# WM8731_STM32F405_Featherwing.net
KiCad netlist of a schematic drawn in EAGLE
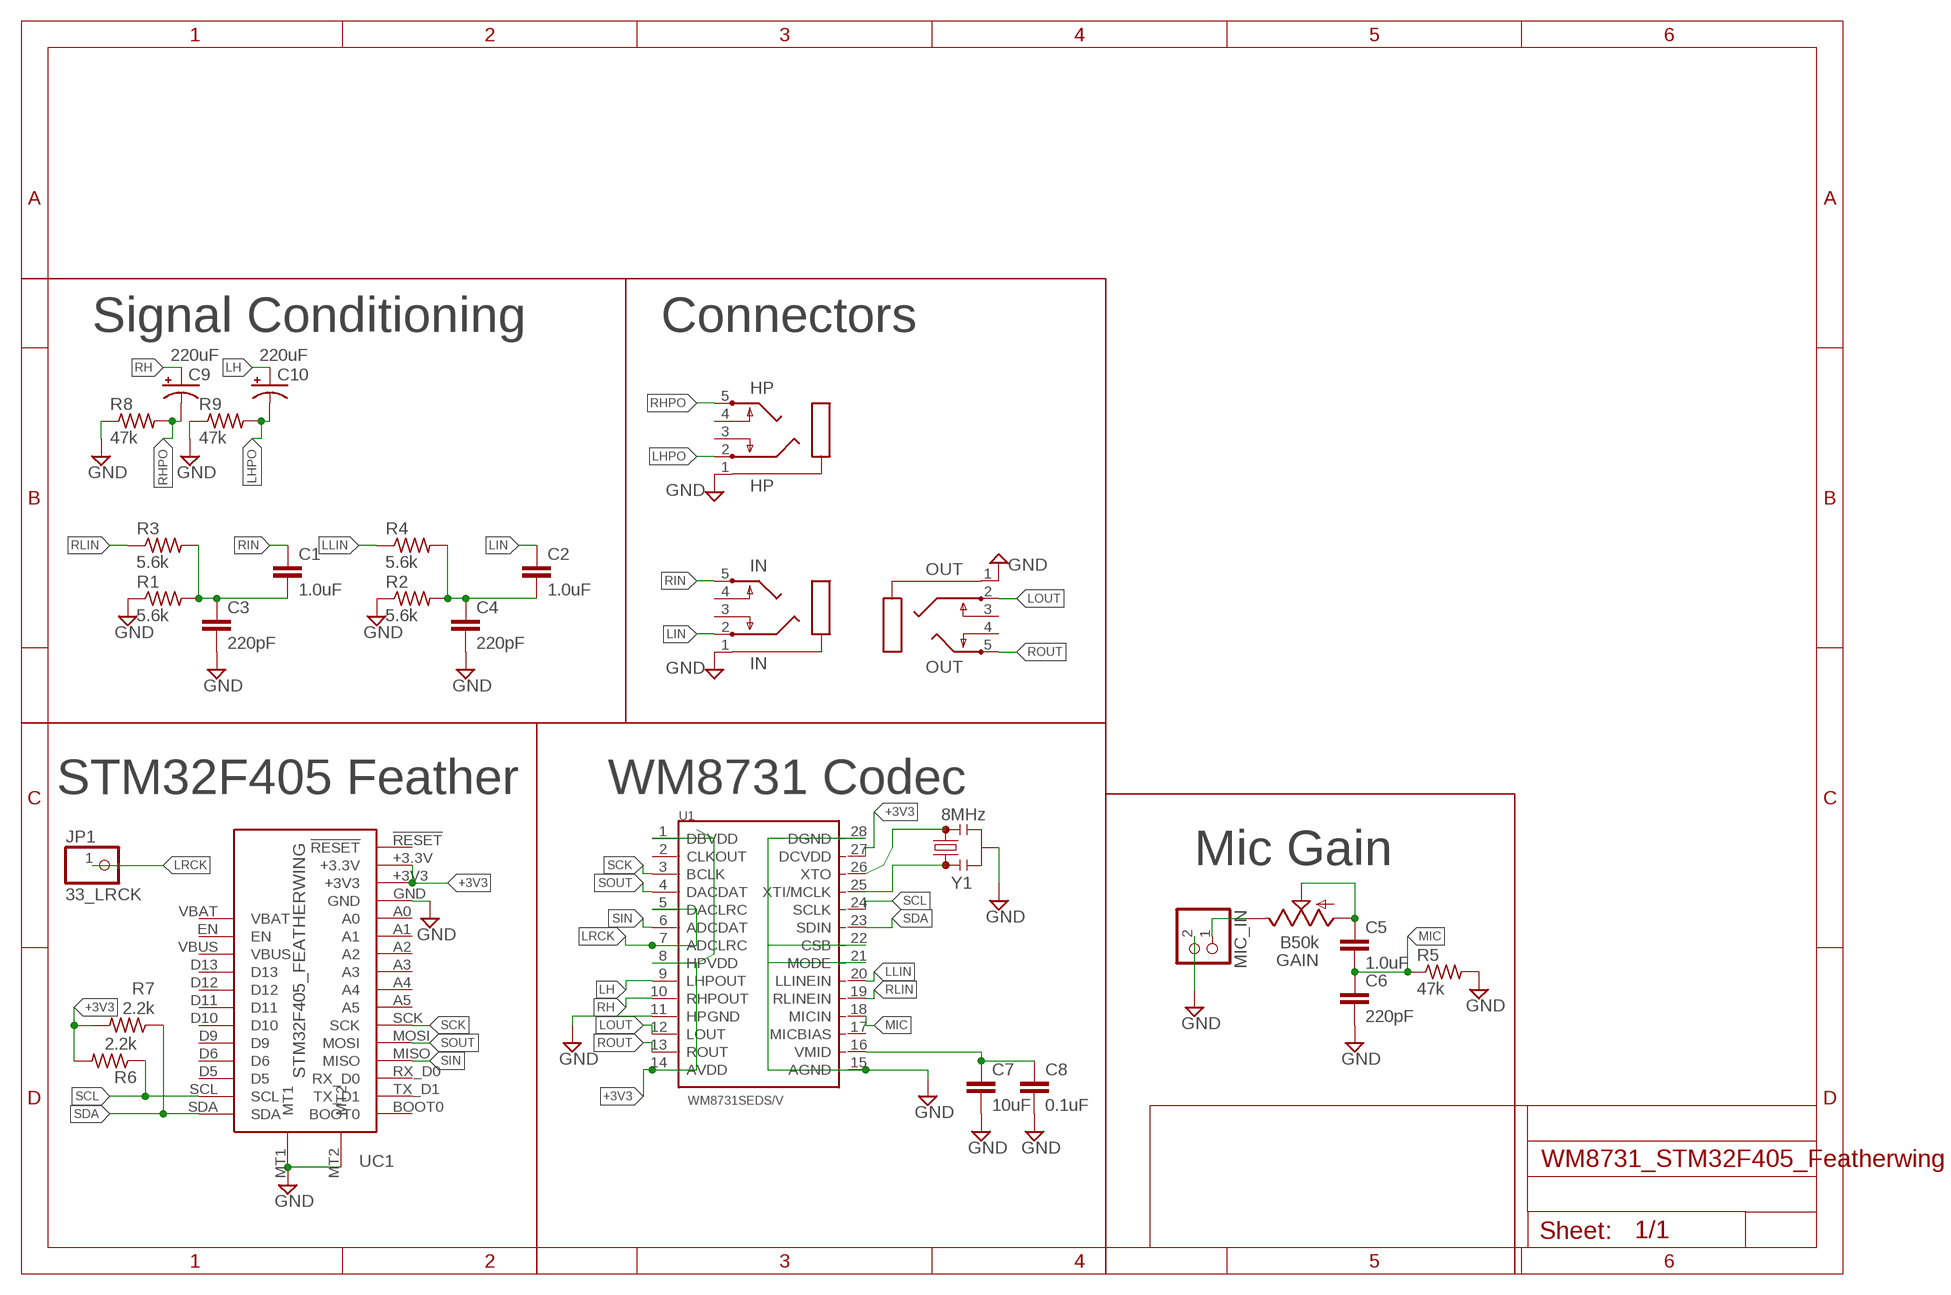
[diagram p0: schematic, sheet 1]

(export (version "E")
  (design (tool "Eeschema 10.0.6"))
  (components
    (comp (ref "C1")
      (value "1.0uF")
      (footprint "eagle-import:0402")
      (libsource (lib "eagle-import") (part "1.0UF-0402-16V-10%"))
    )
    (comp (ref "C2")
      (value "1.0uF")
      (footprint "eagle-import:0402")
      (libsource (lib "eagle-import") (part "1.0UF-0402-16V-10%"))
    )
    (comp (ref "C3")
      (value "220pF")
      (footprint "eagle-import:0402")
      (libsource (lib "eagle-import") (part "1.0UF-0402-16V-10%"))
    )
    (comp (ref "C4")
      (value "220pF")
      (footprint "eagle-import:0402")
      (libsource (lib "eagle-import") (part "1.0UF-0402-16V-10%"))
    )
    (comp (ref "C5")
      (value "1.0uF")
      (footprint "eagle-import:0402")
      (libsource (lib "eagle-import") (part "1.0UF-0402-16V-10%"))
    )
    (comp (ref "C6")
      (value "220pF")
      (footprint "eagle-import:0402")
      (libsource (lib "eagle-import") (part "1.0UF-0402-16V-10%"))
    )
    (comp (ref "C7")
      (value "10uF")
      (footprint "eagle-import:0603")
      (libsource (lib "eagle-import") (part "10UF-0603-6.3V-20%"))
    )
    (comp (ref "C8")
      (value "0.1uF")
      (footprint "eagle-import:0402")
      (libsource (lib "eagle-import") (part "0.1UF-0402-16V-10%"))
    )
    (comp (ref "C9")
      (value "220uF")
      (footprint "eagle-import:PANASONIC_D")
      (libsource (lib "eagle-import") (part "100UF-POLAR-25V-20%(ELEC)"))
    )
    (comp (ref "C10")
      (value "220uF")
      (footprint "eagle-import:PANASONIC_D")
      (libsource (lib "eagle-import") (part "100UF-POLAR-25V-20%(ELEC)"))
    )
    (comp (ref "GAIN")
      (value "B50k")
      (footprint "eagle-import:9MM_SNAP-IN_POT")
      (libsource (lib "eagle-import") (part "9MM_SNAP-IN_POT_"))
    )
    (comp (ref "HP")
      (value "HP")
      (footprint "eagle-import:STX3100")
      (libsource (lib "eagle-import") (part "STEREOJACK"))
    )
    (comp (ref "IN")
      (value "IN")
      (footprint "eagle-import:STX3100")
      (libsource (lib "eagle-import") (part "STEREOJACK"))
    )
    (comp (ref "JP1")
      (value "33_LRCK")
      (footprint "eagle-import:1X01")
      (libsource (lib "eagle-import") (part "PINHD-1X1"))
    )
    (comp (ref "MIC_IN")
      (value "PINHD-1X2")
      (footprint "eagle-import:1X02")
      (libsource (lib "eagle-import") (part "PINHD-1X2"))
    )
    (comp (ref "OUT")
      (value "OUT")
      (footprint "eagle-import:STX3100")
      (libsource (lib "eagle-import") (part "STEREOJACK"))
    )
    (comp (ref "R1")
      (value "5.6k")
      (footprint "eagle-import:R0402")
      (libsource (lib "eagle-import") (part "R-US_R0402"))
    )
    (comp (ref "R2")
      (value "5.6k")
      (footprint "eagle-import:R0402")
      (libsource (lib "eagle-import") (part "R-US_R0402"))
    )
    (comp (ref "R3")
      (value "5.6k")
      (footprint "eagle-import:R0402")
      (libsource (lib "eagle-import") (part "R-US_R0402"))
    )
    (comp (ref "R4")
      (value "5.6k")
      (footprint "eagle-import:R0402")
      (libsource (lib "eagle-import") (part "R-US_R0402"))
    )
    (comp (ref "R5")
      (value "47k")
      (footprint "eagle-import:R0402")
      (libsource (lib "eagle-import") (part "R-US_R0402"))
    )
    (comp (ref "R6")
      (value "2.2k")
      (footprint "eagle-import:R0402")
      (libsource (lib "eagle-import") (part "R-US_R0402"))
    )
    (comp (ref "R7")
      (value "2.2k")
      (footprint "eagle-import:R0402")
      (libsource (lib "eagle-import") (part "R-US_R0402"))
    )
    (comp (ref "R8")
      (value "47k")
      (footprint "eagle-import:R0402")
      (libsource (lib "eagle-import") (part "R-US_R0402"))
    )
    (comp (ref "R9")
      (value "47k")
      (footprint "eagle-import:R0402")
      (libsource (lib "eagle-import") (part "R-US_R0402"))
    )
    (comp (ref "U1")
      (value "WM8731SEDS/V")
      (footprint "eagle-import:SSOP28-0.65-10.2X5.2MM")
      (fields (field (name "MF") "Cirrus Logic"))
      (libsource (lib "eagle-import") (part "CODECODER-WM8731SEDS/V(SSOP28)"))
    )
    (comp (ref "UC1")
      (value "STM32F405_FEATHERWING")
      (footprint "eagle-import:STM32F405_FEATHERWING")
      (libsource (lib "eagle-import") (part "STM32F405_FEATHERWING"))
    )
    (comp (ref "Y1")
      (value "8MHz")
      (footprint "eagle-import:RESONATOR-SMD-3.2X1.3")
      (libsource (lib "eagle-import") (part "RESONATOR-8MHZSMD_3.2X1.3"))
    )
  )
  (nets
    (net (code "1") (name "+3V3") (class "Default")
      (node (ref "R6") (pin "2") (pinfunction "2_2") (pintype "passive"))
      (node (ref "R7") (pin "2") (pinfunction "2_2") (pintype "passive"))
      (node (ref "U1") (pin "1") (pinfunction "DBVDD_1") (pintype "power_in"))
      (node (ref "U1") (pin "14") (pinfunction "AVDD_14") (pintype "power_in"))
      (node (ref "U1") (pin "27") (pinfunction "DCVDD_27") (pintype "power_in"))
      (node (ref "U1") (pin "8") (pinfunction "HPVDD_8") (pintype "power_in"))
      (node (ref "UC1") (pin "+3.3V") (pinfunction "+3.3V_+3.3V") (pintype "bidirectional"))
      (node (ref "UC1") (pin "+3V3") (pinfunction "+3V3_+3V3") (pintype "bidirectional"))
    )
    (net (code "2") (name "GND") (class "Default")
      (node (ref "C3") (pin "2") (pinfunction "2_2") (pintype "passive"))
      (node (ref "C4") (pin "2") (pinfunction "2_2") (pintype "passive"))
      (node (ref "C6") (pin "2") (pinfunction "2_2") (pintype "passive"))
      (node (ref "C7") (pin "2") (pinfunction "2_2") (pintype "passive"))
      (node (ref "C8") (pin "2") (pinfunction "2_2") (pintype "passive"))
      (node (ref "HP") (pin "1") (pinfunction "1_1") (pintype "passive"))
      (node (ref "IN") (pin "1") (pinfunction "1_1") (pintype "passive"))
      (node (ref "MIC_IN") (pin "2") (pinfunction "2_2") (pintype "passive"))
      (node (ref "OUT") (pin "1") (pinfunction "1_1") (pintype "passive"))
      (node (ref "R1") (pin "1") (pinfunction "1_1") (pintype "passive"))
      (node (ref "R2") (pin "1") (pinfunction "1_1") (pintype "passive"))
      (node (ref "R5") (pin "2") (pinfunction "2_2") (pintype "passive"))
      (node (ref "R8") (pin "1") (pinfunction "1_1") (pintype "passive"))
      (node (ref "R9") (pin "1") (pinfunction "1_1") (pintype "passive"))
      (node (ref "U1") (pin "11") (pinfunction "HPGND_11") (pintype "bidirectional"))
      (node (ref "U1") (pin "15") (pinfunction "AGND_15") (pintype "power_in"))
      (node (ref "U1") (pin "21") (pinfunction "MODE_21") (pintype "bidirectional"))
      (node (ref "U1") (pin "22") (pinfunction "CSB_22") (pintype "bidirectional"))
      (node (ref "U1") (pin "28") (pinfunction "DGND_28") (pintype "power_in"))
      (node (ref "UC1") (pin "GND") (pinfunction "GND_GND") (pintype "bidirectional"))
      (node (ref "UC1") (pin "MT1") (pinfunction "MT1_MT1") (pintype "bidirectional"))
      (node (ref "UC1") (pin "MT2") (pinfunction "MT2_MT2") (pintype "bidirectional"))
      (node (ref "Y1") (pin "2") (pinfunction "2_2") (pintype "passive"))
    )
    (net (code "3") (name "LH") (class "Default")
      (node (ref "C10") (pin "+") (pinfunction "+_+") (pintype "passive"))
      (node (ref "U1") (pin "9") (pinfunction "LHPOUT_9") (pintype "bidirectional"))
    )
    (net (code "4") (name "LHPO") (class "Default")
      (node (ref "C10") (pin "-") (pinfunction "-_-") (pintype "passive"))
      (node (ref "HP") (pin "2") (pinfunction "2_2") (pintype "passive"))
      (node (ref "R9") (pin "2") (pinfunction "2_2") (pintype "passive"))
    )
    (net (code "5") (name "LIN") (class "Default")
      (node (ref "C2") (pin "1") (pinfunction "1_1") (pintype "passive"))
      (node (ref "IN") (pin "2") (pinfunction "2_2") (pintype "passive"))
    )
    (net (code "6") (name "LLIN") (class "Default")
      (node (ref "R4") (pin "1") (pinfunction "1_1") (pintype "passive"))
      (node (ref "U1") (pin "20") (pinfunction "LLINEIN_20") (pintype "bidirectional"))
    )
    (net (code "7") (name "LOUT") (class "Default")
      (node (ref "OUT") (pin "2") (pinfunction "2_2") (pintype "passive"))
      (node (ref "U1") (pin "12") (pinfunction "LOUT_12") (pintype "bidirectional"))
    )
    (net (code "8") (name "LRCK") (class "Default")
      (node (ref "JP1") (pin "1") (pinfunction "1_1") (pintype "passive"))
      (node (ref "U1") (pin "5") (pinfunction "DACLRC_5") (pintype "bidirectional"))
      (node (ref "U1") (pin "7") (pinfunction "ADCLRC_7") (pintype "bidirectional"))
    )
    (net (code "9") (name "MIC") (class "Default")
      (node (ref "C5") (pin "2") (pinfunction "2_2") (pintype "passive"))
      (node (ref "C6") (pin "1") (pinfunction "1_1") (pintype "passive"))
      (node (ref "R5") (pin "1") (pinfunction "1_1") (pintype "passive"))
      (node (ref "U1") (pin "18") (pinfunction "MICIN_18") (pintype "bidirectional"))
    )
    (net (code "10") (name "Net-(C1-Pad2)") (class "Default")
      (node (ref "C1") (pin "2") (pinfunction "2_2") (pintype "passive"))
      (node (ref "C3") (pin "1") (pinfunction "1_1") (pintype "passive"))
      (node (ref "R1") (pin "2") (pinfunction "2_2") (pintype "passive"))
      (node (ref "R3") (pin "2") (pinfunction "2_2") (pintype "passive"))
    )
    (net (code "11") (name "Net-(C2-Pad2)") (class "Default")
      (node (ref "C2") (pin "2") (pinfunction "2_2") (pintype "passive"))
      (node (ref "C4") (pin "1") (pinfunction "1_1") (pintype "passive"))
      (node (ref "R2") (pin "2") (pinfunction "2_2") (pintype "passive"))
      (node (ref "R4") (pin "2") (pinfunction "2_2") (pintype "passive"))
    )
    (net (code "12") (name "Net-(GAIN-A)") (class "Default")
      (node (ref "C5") (pin "1") (pinfunction "1_1") (pintype "passive"))
      (node (ref "GAIN") (pin "1") (pinfunction "A_1") (pintype "passive"))
      (node (ref "GAIN") (pin "2") (pinfunction "S_2") (pintype "passive"))
    )
    (net (code "13") (name "Net-(GAIN-E)") (class "Default")
      (node (ref "GAIN") (pin "3") (pinfunction "E_3") (pintype "passive"))
      (node (ref "MIC_IN") (pin "1") (pinfunction "1_1") (pintype "passive"))
    )
    (net (code "14") (name "Net-(U1-VMID)") (class "Default")
      (node (ref "C7") (pin "1") (pinfunction "1_1") (pintype "passive"))
      (node (ref "C8") (pin "1") (pinfunction "1_1") (pintype "passive"))
      (node (ref "U1") (pin "16") (pinfunction "VMID_16") (pintype "bidirectional"))
    )
    (net (code "15") (name "Net-(U1-XTI{slash}MCLK)") (class "Default")
      (node (ref "U1") (pin "25") (pinfunction "XTI/MCLK_25") (pintype "bidirectional"))
      (node (ref "Y1") (pin "1") (pinfunction "1_1") (pintype "passive"))
    )
    (net (code "16") (name "Net-(U1-XTO)") (class "Default")
      (node (ref "U1") (pin "26") (pinfunction "XTO_26") (pintype "bidirectional"))
      (node (ref "Y1") (pin "3") (pinfunction "3_3") (pintype "passive"))
    )
    (net (code "17") (name "RH") (class "Default")
      (node (ref "C9") (pin "+") (pinfunction "+_+") (pintype "passive"))
      (node (ref "U1") (pin "10") (pinfunction "RHPOUT_10") (pintype "bidirectional"))
    )
    (net (code "18") (name "RHPO") (class "Default")
      (node (ref "C9") (pin "-") (pinfunction "-_-") (pintype "passive"))
      (node (ref "HP") (pin "5") (pinfunction "5_5") (pintype "passive"))
      (node (ref "R8") (pin "2") (pinfunction "2_2") (pintype "passive"))
    )
    (net (code "19") (name "RIN") (class "Default")
      (node (ref "C1") (pin "1") (pinfunction "1_1") (pintype "passive"))
      (node (ref "IN") (pin "5") (pinfunction "5_5") (pintype "passive"))
    )
    (net (code "20") (name "RLIN") (class "Default")
      (node (ref "R3") (pin "1") (pinfunction "1_1") (pintype "passive"))
      (node (ref "U1") (pin "19") (pinfunction "RLINEIN_19") (pintype "bidirectional"))
    )
    (net (code "21") (name "ROUT") (class "Default")
      (node (ref "OUT") (pin "5") (pinfunction "5_5") (pintype "passive"))
      (node (ref "U1") (pin "13") (pinfunction "ROUT_13") (pintype "bidirectional"))
    )
    (net (code "22") (name "SCK") (class "Default")
      (node (ref "U1") (pin "3") (pinfunction "BCLK_3") (pintype "bidirectional"))
      (node (ref "UC1") (pin "SCK") (pinfunction "SCK_SCK") (pintype "bidirectional"))
    )
    (net (code "23") (name "SCL") (class "Default")
      (node (ref "R6") (pin "1") (pinfunction "1_1") (pintype "passive"))
      (node (ref "U1") (pin "24") (pinfunction "SCLK_24") (pintype "bidirectional"))
      (node (ref "UC1") (pin "SCL") (pinfunction "SCL_SCL") (pintype "bidirectional"))
    )
    (net (code "24") (name "SDA") (class "Default")
      (node (ref "R7") (pin "1") (pinfunction "1_1") (pintype "passive"))
      (node (ref "U1") (pin "23") (pinfunction "SDIN_23") (pintype "bidirectional"))
      (node (ref "UC1") (pin "SDA") (pinfunction "SDA_SDA") (pintype "bidirectional"))
    )
    (net (code "25") (name "SIN") (class "Default")
      (node (ref "U1") (pin "6") (pinfunction "ADCDAT_6") (pintype "bidirectional"))
      (node (ref "UC1") (pin "MISO") (pinfunction "MISO_MISO") (pintype "bidirectional"))
    )
    (net (code "26") (name "SOUT") (class "Default")
      (node (ref "U1") (pin "4") (pinfunction "DACDAT_4") (pintype "bidirectional"))
      (node (ref "UC1") (pin "MOSI") (pinfunction "MOSI_MOSI") (pintype "bidirectional"))
    )
    (net (code "27") (name "unconnected-(HP-Pad3)") (class "Default")
      (node (ref "HP") (pin "3") (pinfunction "3_3") (pintype "passive"))
    )
    (net (code "28") (name "unconnected-(HP-Pad4)") (class "Default")
      (node (ref "HP") (pin "4") (pinfunction "4_4") (pintype "passive"))
    )
    (net (code "29") (name "unconnected-(IN-Pad3)") (class "Default")
      (node (ref "IN") (pin "3") (pinfunction "3_3") (pintype "passive"))
    )
    (net (code "30") (name "unconnected-(IN-Pad4)") (class "Default")
      (node (ref "IN") (pin "4") (pinfunction "4_4") (pintype "passive"))
    )
    (net (code "31") (name "unconnected-(OUT-Pad3)") (class "Default")
      (node (ref "OUT") (pin "3") (pinfunction "3_3") (pintype "passive"))
    )
    (net (code "32") (name "unconnected-(OUT-Pad4)") (class "Default")
      (node (ref "OUT") (pin "4") (pinfunction "4_4") (pintype "passive"))
    )
    (net (code "33") (name "unconnected-(U1-CLKOUT-Pad2)") (class "Default")
      (node (ref "U1") (pin "2") (pinfunction "CLKOUT_2") (pintype "bidirectional"))
    )
    (net (code "34") (name "unconnected-(U1-MICBIAS-Pad17)") (class "Default")
      (node (ref "U1") (pin "17") (pinfunction "MICBIAS_17") (pintype "bidirectional"))
    )
    (net (code "35") (name "unconnected-(UC1-PadA0)") (class "Default")
      (node (ref "UC1") (pin "A0") (pinfunction "A0_A0") (pintype "bidirectional"))
    )
    (net (code "36") (name "unconnected-(UC1-PadA1)") (class "Default")
      (node (ref "UC1") (pin "A1") (pinfunction "A1_A1") (pintype "bidirectional"))
    )
    (net (code "37") (name "unconnected-(UC1-PadA2)") (class "Default")
      (node (ref "UC1") (pin "A2") (pinfunction "A2_A2") (pintype "bidirectional"))
    )
    (net (code "38") (name "unconnected-(UC1-PadA3)") (class "Default")
      (node (ref "UC1") (pin "A3") (pinfunction "A3_A3") (pintype "bidirectional"))
    )
    (net (code "39") (name "unconnected-(UC1-PadA4)") (class "Default")
      (node (ref "UC1") (pin "A4") (pinfunction "A4_A4") (pintype "bidirectional"))
    )
    (net (code "40") (name "unconnected-(UC1-PadA5)") (class "Default")
      (node (ref "UC1") (pin "A5") (pinfunction "A5_A5") (pintype "bidirectional"))
    )
    (net (code "41") (name "unconnected-(UC1-PadBOOT0)") (class "Default")
      (node (ref "UC1") (pin "BOOT0") (pinfunction "BOOT0_BOOT0") (pintype "bidirectional"))
    )
    (net (code "42") (name "unconnected-(UC1-PadD5)") (class "Default")
      (node (ref "UC1") (pin "D5") (pinfunction "D5_D5") (pintype "bidirectional"))
    )
    (net (code "43") (name "unconnected-(UC1-PadD6)") (class "Default")
      (node (ref "UC1") (pin "D6") (pinfunction "D6_D6") (pintype "bidirectional"))
    )
    (net (code "44") (name "unconnected-(UC1-PadD9)") (class "Default")
      (node (ref "UC1") (pin "D9") (pinfunction "D9_D9") (pintype "bidirectional"))
    )
    (net (code "45") (name "unconnected-(UC1-PadD10)") (class "Default")
      (node (ref "UC1") (pin "D10") (pinfunction "D10_D10") (pintype "bidirectional"))
    )
    (net (code "46") (name "unconnected-(UC1-PadD11)") (class "Default")
      (node (ref "UC1") (pin "D11") (pinfunction "D11_D11") (pintype "bidirectional"))
    )
    (net (code "47") (name "unconnected-(UC1-PadD12)") (class "Default")
      (node (ref "UC1") (pin "D12") (pinfunction "D12_D12") (pintype "bidirectional"))
    )
    (net (code "48") (name "unconnected-(UC1-PadD13)") (class "Default")
      (node (ref "UC1") (pin "D13") (pinfunction "D13_D13") (pintype "bidirectional"))
    )
    (net (code "49") (name "unconnected-(UC1-PadEN)") (class "Default")
      (node (ref "UC1") (pin "EN") (pinfunction "EN_EN") (pintype "bidirectional"))
    )
    (net (code "50") (name "unconnected-(UC1-PadRX_D0)") (class "Default")
      (node (ref "UC1") (pin "RX_D0") (pinfunction "RX_D0_RX_D0") (pintype "bidirectional"))
    )
    (net (code "51") (name "unconnected-(UC1-PadTX_D1)") (class "Default")
      (node (ref "UC1") (pin "TX_D1") (pinfunction "TX_D1_TX_D1") (pintype "bidirectional"))
    )
    (net (code "52") (name "unconnected-(UC1-PadVBAT)") (class "Default")
      (node (ref "UC1") (pin "VBAT") (pinfunction "VBAT_VBAT") (pintype "bidirectional"))
    )
    (net (code "53") (name "unconnected-(UC1-PadVBUS)") (class "Default")
      (node (ref "UC1") (pin "VBUS") (pinfunction "VBUS_VBUS") (pintype "bidirectional"))
    )
    (net (code "54") (name "unconnected-(UC1-~{RESET}-Pad!RESET!)") (class "Default")
      (node (ref "UC1") (pin "!RESET!") (pinfunction "~{RESET}_!RESET!") (pintype "bidirectional"))
    )
  )
)
